# Buck_Converter.net
KiCad netlist of a schematic drawn in Altium Designer
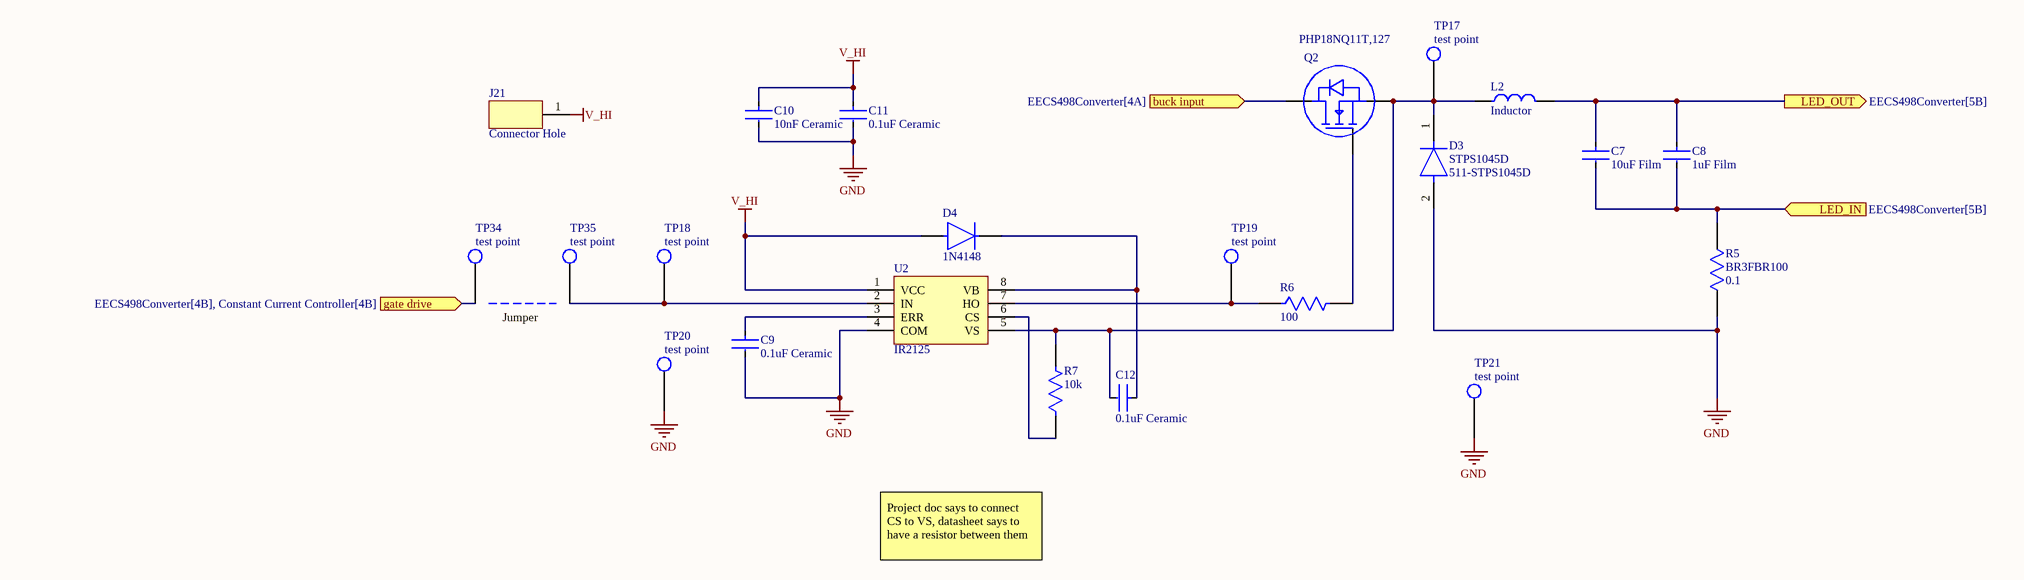
[diagram p0: Buck Converter.SchDoc]

(export (version "E")
  (design (tool "Eeschema 10.0.6"))
  (components
    (comp (ref "C7")
      (value "10uF Film")
      (footprint "FP-FILM-CAP-22.5mm")
      (description "CAP CER 10UF 50V X7R FILM")
      (fields (field (name "TOLERANCE") "10%") (field (name "VOLTAGE") "50V"))
      (libsource (lib "EECS498Converter") (part "10uF Capacitor"))
    )
    (comp (ref "C8")
      (value "1uF Film")
      (footprint "FP-FILM-CAP-10mm")
      (description "CAP CER 1UF 50V X7R FILM")
      (fields (field (name "TOLERANCE") "10%") (field (name "VOLTAGE") "50V"))
      (libsource (lib "EECS498Converter") (part "1uf Capacitor"))
    )
    (comp (ref "C9")
      (value "0.1uF Ceramic")
      (footprint "FP-K15H5-MFG")
      (description "CAP CER 0.1UF 50V X7R RADIAL")
      (fields (field (name "TOLERANCE") "10%") (field (name "VOLTAGE") "50V"))
      (libsource (lib "EECS498Converter") (part "0.1uF Capacitor"))
    )
    (comp (ref "C10")
      (value "10nF Ceramic")
      (footprint "FP-K15H5-MFG")
      (description "CAP CER 10nF 50V X7R RADIAL")
      (fields (field (name "TOLERANCE") "10%") (field (name "VOLTAGE") "50V"))
      (libsource (lib "EECS498Converter") (part "10nF Capacitor"))
    )
    (comp (ref "C11")
      (value "0.1uF Ceramic")
      (footprint "FP-K15H5-MFG")
      (description "CAP CER 0.1UF 50V X7R RADIAL")
      (fields (field (name "TOLERANCE") "10%") (field (name "VOLTAGE") "50V"))
      (libsource (lib "EECS498Converter") (part "0.1uF Capacitor"))
    )
    (comp (ref "C12")
      (value "0.1uF Ceramic")
      (footprint "FP-K15H5-MFG")
      (description "CAP CER 0.1UF 50V X7R RADIAL")
      (fields (field (name "TOLERANCE") "10%") (field (name "VOLTAGE") "50V"))
      (libsource (lib "EECS498Converter") (part "0.1uF Capacitor"))
    )
    (comp (ref "D3")
      (value "STPS1045D")
      (footprint "STPS1045D")
      (description "Diode 45 V 10A Through Hole TO-220AC")
      (fields (field (name "SUPPLIER PART NUMBER 1") "511-STPS1045D"))
      (libsource (lib "EECS498Converter") (part "STPS1045D"))
    )
    (comp (ref "D4")
      (value "1N4148")
      (footprint "FP-1N4148-MFG")
      (description "DIODE GEN PURP 100V 200MA DO35")
      (fields (field (name "VOLTAGE") "100V"))
      (libsource (lib "EECS498Converter") (part "1N4148"))
    )
    (comp (ref "J21")
      (value "Connector Hole")
      (footprint "Connector Hole")
      (libsource (lib "EECS498Converter") (part "Connector Hole"))
    )
    (comp (ref "L2")
      (value "Inductor")
      (footprint "Power Inductor")
      (fields (field (name "TOLERANCE") "10%"))
      (libsource (lib "EECS498Converter") (part "Inductor"))
    )
    (comp (ref "Q2")
      (value "PHP18NQ11T,127")
      (footprint "1727-PHP18NQ11T,127-ND")
      (description "N-Channel 110 V 18A (Tc) 79W (Tc) Through Hole TO-220AB")
      (libsource (lib "EECS498Converter") (part "PHP18NQ11T,127"))
    )
    (comp (ref "R5")
      (value "BR3FBR100")
      (footprint "BR3FBR100")
      (fields (field (name "ALTIUM_VALUE") "0.1"))
      (libsource (lib "EECS498Converter") (part "BR3FBR100"))
    )
    (comp (ref "R6")
      (value "100")
      (footprint "FP-RLR07-MFG")
      (description "Resistor, ± 1%, 250 mW, Axial Leaded, Metal Film, Military Reliability")
      (fields (field (name "TOLERANCE") "1%"))
      (libsource (lib "EECS498Converter") (part "Resistor"))
    )
    (comp (ref "R7")
      (value "10k")
      (footprint "FP-RLR07-MFG")
      (description "Resistor, ± 1%, 250 mW, Axial Leaded, Metal Film, Military Reliability")
      (fields (field (name "TOLERANCE") "1%"))
      (libsource (lib "EECS498Converter") (part "Resistor"))
    )
    (comp (ref "TP17")
      (value "test point")
      (footprint "test point")
      (libsource (lib "EECS498Converter") (part "test point"))
    )
    (comp (ref "TP18")
      (value "test point")
      (footprint "test point")
      (libsource (lib "EECS498Converter") (part "test point"))
    )
    (comp (ref "TP19")
      (value "test point")
      (footprint "test point")
      (libsource (lib "EECS498Converter") (part "test point"))
    )
    (comp (ref "TP20")
      (value "test point")
      (footprint "test point")
      (libsource (lib "EECS498Converter") (part "test point"))
    )
    (comp (ref "TP21")
      (value "test point")
      (footprint "test point")
      (libsource (lib "EECS498Converter") (part "test point"))
    )
    (comp (ref "TP34")
      (value "test point")
      (footprint "test point")
      (libsource (lib "EECS498Converter") (part "test point"))
    )
    (comp (ref "TP35")
      (value "test point")
      (footprint "test point")
      (libsource (lib "EECS498Converter") (part "test point"))
    )
    (comp (ref "U2")
      (value "IR2125")
      (footprint "DIP8")
      (description "High-Side Gate Driver IC Non-Inverting 8-PDIP")
      (libsource (lib "EECS498Converter") (part "IR2125"))
    )
  )
  (nets
    (net (code "1") (name "/LED_IN") (class "Default")
      (node (ref "C7") (pin "2") (pinfunction "2_2") (pintype "passive"))
      (node (ref "C8") (pin "2") (pinfunction "2_2") (pintype "passive"))
      (node (ref "R5") (pin "2") (pintype "passive"))
    )
    (net (code "2") (name "/LED_OUT") (class "Default")
      (node (ref "C7") (pin "1") (pinfunction "1_1") (pintype "passive"))
      (node (ref "C8") (pin "1") (pinfunction "1_1") (pintype "passive"))
      (node (ref "L2") (pin "2") (pinfunction "2_2") (pintype "passive"))
    )
    (net (code "3") (name "/buck input") (class "Default")
      (node (ref "Q2") (pin "2") (pinfunction "D_2") (pintype "passive"))
    )
    (net (code "4") (name "/gate drive") (class "Default") (node (ref "TP34") (pin "1") (pintype "passive")))
    (net (code "5") (name "GND") (class "Default")
      (node (ref "C10") (pin "2") (pinfunction "2_2") (pintype "passive"))
      (node (ref "C11") (pin "2") (pinfunction "2_2") (pintype "passive"))
      (node (ref "C9") (pin "2") (pinfunction "2_2") (pintype "passive"))
      (node (ref "D3") (pin "2") (pinfunction "A_2") (pintype "passive"))
      (node (ref "R5") (pin "1") (pintype "passive"))
      (node (ref "TP20") (pin "1") (pintype "passive"))
      (node (ref "TP21") (pin "1") (pintype "passive"))
      (node (ref "U2") (pin "4") (pinfunction "COM_4") (pintype "passive"))
    )
    (net (code "6") (name "Net-(D3-K)") (class "Default")
      (node (ref "C12") (pin "2") (pinfunction "2_2") (pintype "passive"))
      (node (ref "D3") (pin "1") (pinfunction "K_1") (pintype "passive"))
      (node (ref "L2") (pin "1") (pinfunction "1_1") (pintype "passive"))
      (node (ref "Q2") (pin "3") (pinfunction "S_3") (pintype "passive"))
      (node (ref "R7") (pin "2") (pinfunction "2_2") (pintype "passive"))
      (node (ref "TP17") (pin "1") (pintype "passive"))
      (node (ref "U2") (pin "5") (pinfunction "VS_5") (pintype "passive"))
    )
    (net (code "7") (name "Net-(D4-C)") (class "Default")
      (node (ref "C12") (pin "1") (pinfunction "1_1") (pintype "passive"))
      (node (ref "D4") (pin "1") (pinfunction "C_1") (pintype "passive"))
      (node (ref "U2") (pin "8") (pinfunction "VB_8") (pintype "passive"))
    )
    (net (code "8") (name "Net-(Q2-G)") (class "Default")
      (node (ref "Q2") (pin "1") (pinfunction "G_1") (pintype "passive"))
      (node (ref "R6") (pin "2") (pinfunction "2_2") (pintype "passive"))
    )
    (net (code "9") (name "Net-(U2-CS)") (class "Default")
      (node (ref "R7") (pin "1") (pinfunction "1_1") (pintype "passive"))
      (node (ref "U2") (pin "6") (pinfunction "CS_6") (pintype "passive"))
    )
    (net (code "10") (name "Net-(U2-ERR)") (class "Default")
      (node (ref "C9") (pin "1") (pinfunction "1_1") (pintype "passive"))
      (node (ref "U2") (pin "3") (pinfunction "ERR_3") (pintype "passive"))
    )
    (net (code "11") (name "Net-(U2-HO)") (class "Default")
      (node (ref "R6") (pin "1") (pinfunction "1_1") (pintype "passive"))
      (node (ref "TP19") (pin "1") (pintype "passive"))
      (node (ref "U2") (pin "7") (pinfunction "HO_7") (pintype "passive"))
    )
    (net (code "12") (name "Net-(U2-IN)") (class "Default")
      (node (ref "TP18") (pin "1") (pintype "passive"))
      (node (ref "TP35") (pin "1") (pintype "passive"))
      (node (ref "U2") (pin "2") (pinfunction "IN_2") (pintype "passive"))
    )
    (net (code "13") (name "V_HI") (class "Default")
      (node (ref "C10") (pin "1") (pinfunction "1_1") (pintype "passive"))
      (node (ref "C11") (pin "1") (pinfunction "1_1") (pintype "passive"))
      (node (ref "D4") (pin "2") (pinfunction "A_2") (pintype "passive"))
      (node (ref "J21") (pin "1") (pinfunction "1_1") (pintype "passive"))
      (node (ref "U2") (pin "1") (pinfunction "VCC_1") (pintype "passive"))
    )
  )
)
